# FEU31_Part2.net
KiCad netlist of a schematic drawn in Altium Designer
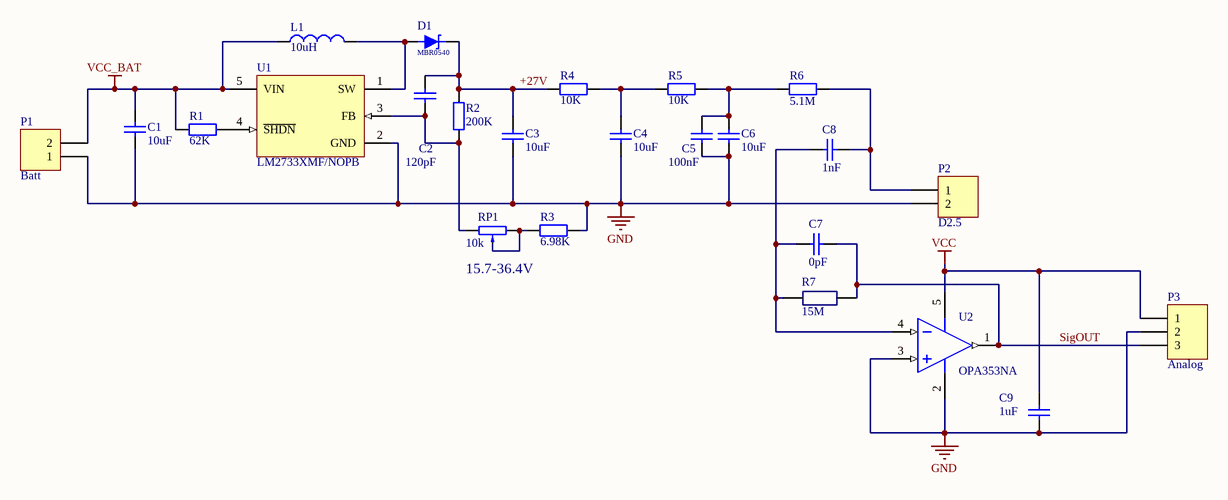
[diagram p0: FEU31_Part2.SchDoc]

(export (version "E")
  (design (tool "Eeschema 10.0.6"))
  (components
    (comp (ref "C1")
      (value "10uF")
      (footprint "Miscellaneous Devices:C1206")
      (description "Capacitor (Semiconductor SIM Model)")
      (fields (field (name "PUBLISHER") "Altium Limited"))
      (libsource (lib "Miscellaneous Devices") (part "Cap Semi"))
    )
    (comp (ref "C2")
      (value "120pF")
      (footprint "1608[0603]")
      (description "Capacitor (Semiconductor SIM Model)")
      (fields (field (name "PUBLISHER") "Altium Limited"))
      (libsource (lib "Miscellaneous Devices") (part "Cap Semi"))
    )
    (comp (ref "C3")
      (value "10uF")
      (footprint "Miscellaneous Devices:C1206")
      (description "Capacitor (Semiconductor SIM Model)")
      (fields (field (name "PUBLISHER") "Altium Limited"))
      (libsource (lib "Miscellaneous Devices") (part "Cap Semi"))
    )
    (comp (ref "C4")
      (value "10uF")
      (footprint "Miscellaneous Devices:C1206")
      (description "Capacitor (Semiconductor SIM Model)")
      (fields (field (name "PUBLISHER") "Altium Limited"))
      (libsource (lib "Miscellaneous Devices") (part "Cap Semi"))
    )
    (comp (ref "C5")
      (value "100nF")
      (footprint "1608[0603]")
      (description "Capacitor (Semiconductor SIM Model)")
      (fields (field (name "PUBLISHER") "Altium Limited"))
      (libsource (lib "Miscellaneous Devices") (part "Cap Semi"))
    )
    (comp (ref "C6")
      (value "10uF")
      (footprint "Miscellaneous Devices:C1206")
      (description "Capacitor (Semiconductor SIM Model)")
      (fields (field (name "PUBLISHER") "Altium Limited"))
      (libsource (lib "Miscellaneous Devices") (part "Cap Semi"))
    )
    (comp (ref "C7")
      (value "0pF")
      (footprint "1608[0603]")
      (description "Capacitor (Semiconductor SIM Model)")
      (fields (field (name "PUBLISHER") "Altium Limited"))
      (libsource (lib "Miscellaneous Devices") (part "Cap Semi"))
    )
    (comp (ref "C8")
      (value "1nF")
      (footprint "1608[0603]")
      (description "Capacitor (Semiconductor SIM Model)")
      (fields (field (name "PUBLISHER") "Altium Limited"))
      (libsource (lib "Miscellaneous Devices") (part "Cap Semi"))
    )
    (comp (ref "C9")
      (value "1uF")
      (footprint "1608[0603]_CAP")
      (description "Capacitor (Semiconductor SIM Model)")
      (fields (field (name "PUBLISHER") "Altium Limited"))
      (libsource (lib "Miscellaneous Devices") (part "Cap Semi"))
    )
    (comp (ref "D1")
      (value "MBR0540")
      (footprint "SOD123")
      (description "SMD 40V 0.5A")
      (libsource (lib "Diodes-Power") (part "MBR0540"))
    )
    (comp (ref "L1")
      (value "10uH")
      (footprint "IFSC1515AHER100M01")
      (description "Inductor")
      (fields (field (name "PUBLISHER") "Altium Limited"))
      (libsource (lib "Miscellaneous Devices") (part "Inductor"))
    )
    (comp (ref "P1")
      (value "Batt")
      (footprint "HDR1X2")
      (description "Header, 2-Pin")
      (fields (field (name "PUBLISHER") "Altium Limited"))
      (libsource (lib "Miscellaneous Connectors") (part "Header 2"))
    )
    (comp (ref "P2")
      (value "D2.5")
      (footprint "HDR1X2")
      (description "Header, 2-Pin")
      (fields (field (name "PUBLISHER") "Altium Limited"))
      (libsource (lib "") (part "Header 2_1"))
    )
    (comp (ref "P3")
      (value "Analog")
      (footprint "HDR1X3")
      (description "Header, 3-Pin")
      (fields (field (name "PUBLISHER") "Altium Limited"))
      (libsource (lib "Miscellaneous Connectors") (part "Header 3"))
    )
    (comp (ref "R1")
      (value "62K")
      (footprint "1608[0603]_RES")
      (description "Resistor")
      (fields (field (name "PUBLISHER") "Altium Limited"))
      (libsource (lib "Miscellaneous Devices") (part "Res2"))
    )
    (comp (ref "R2")
      (value "200K")
      (footprint "1608[0603]_RES")
      (description "Resistor")
      (fields (field (name "PUBLISHER") "Altium Limited"))
      (libsource (lib "") (part "Res2_2"))
    )
    (comp (ref "R3")
      (value "6.98K")
      (footprint "1608[0603]_RES")
      (description "Resistor")
      (fields (field (name "PUBLISHER") "Altium Limited"))
      (libsource (lib "") (part "Res2_1"))
    )
    (comp (ref "R4")
      (value "10K")
      (footprint "1608[0603]_RES")
      (description "Resistor")
      (fields (field (name "PUBLISHER") "Altium Limited"))
      (libsource (lib "Miscellaneous Devices") (part "Res2"))
    )
    (comp (ref "R5")
      (value "10K")
      (footprint "1608[0603]_RES")
      (description "Resistor")
      (fields (field (name "PUBLISHER") "Altium Limited"))
      (libsource (lib "Miscellaneous Devices") (part "Res2"))
    )
    (comp (ref "R6")
      (value "5.1M")
      (footprint "1608[0603]_RES")
      (description "Resistor")
      (fields (field (name "PUBLISHER") "Altium Limited"))
      (libsource (lib "Miscellaneous Devices") (part "Res2"))
    )
    (comp (ref "R7")
      (value "15M")
      (footprint "1608[0603]_RES")
      (libsource (lib "Микрон-3") (part "Resistor 0805"))
    )
    (comp (ref "RP1")
      (value "10k")
      (footprint "3224W")
      (description "Bourns 3296W 0.5W 25 Turns")
      (libsource (lib "Rez-Axial Pot") (part "R-Tr 3296W (64W)"))
    )
    (comp (ref "U1")
      (value "LM2733XMF/NOPB")
      (footprint "MF05A_N")
      (description "0.6/1.6 MHz Boost Converters With 40V Internal FET Switch in 5-pin SOT-23, Pb-Free")
      (fields
        (field (name "MANUFACTURER") "National Semiconductor")
        (field (name "PUBLISHER") "Altium Limited")
      )
      (libsource (lib "NSC Switcher") (part "LM2733XMF/NOPB"))
    )
    (comp (ref "U2")
      (value "OPA353NA")
      (footprint "ADI-RJ-5_N")
      (fields
        (field (name "GENERIC PART NUMBER") "AD8541")
        (field (name "MANUFACTURER") "Analog Devices")
        (field (name "PARTNUMBER") "AD8541ARTZ-R2")
      )
      (libsource (lib "Analog Devices Operational Amplifiers") (part "AD8541ARTZ-R2"))
    )
  )
  (nets
    (net (code "1") (name "/+27V") (class "Default")
      (node (ref "C2") (pin "2") (pinfunction "2_2") (pintype "passive"))
      (node (ref "C3") (pin "1") (pinfunction "1_1") (pintype "passive"))
      (node (ref "D1") (pin "2") (pinfunction "K_2") (pintype "passive"))
      (node (ref "R2") (pin "1") (pinfunction "1_1") (pintype "passive"))
      (node (ref "R4") (pin "2") (pinfunction "2_2") (pintype "passive"))
    )
    (net (code "2") (name "/SigOUT") (class "Default")
      (node (ref "C7") (pin "2") (pinfunction "2_2") (pintype "passive"))
      (node (ref "P3") (pin "3") (pinfunction "3_3") (pintype "passive"))
      (node (ref "R7") (pin "2") (pinfunction "2_2") (pintype "passive"))
      (node (ref "U2") (pin "1") (pinfunction "OUT_A_1") (pintype "output"))
    )
    (net (code "3") (name "GND") (class "Default")
      (node (ref "C1") (pin "2") (pinfunction "2_2") (pintype "passive"))
      (node (ref "C3") (pin "2") (pinfunction "2_2") (pintype "passive"))
      (node (ref "C4") (pin "2") (pinfunction "2_2") (pintype "passive"))
      (node (ref "C5") (pin "1") (pinfunction "1_1") (pintype "passive"))
      (node (ref "C6") (pin "2") (pinfunction "2_2") (pintype "passive"))
      (node (ref "C9") (pin "2") (pinfunction "2_2") (pintype "passive"))
      (node (ref "P1") (pin "1") (pinfunction "1_1") (pintype "passive"))
      (node (ref "P2") (pin "2") (pinfunction "2_2") (pintype "passive"))
      (node (ref "P3") (pin "2") (pinfunction "2_2") (pintype "passive"))
      (node (ref "R3") (pin "2") (pinfunction "2_2") (pintype "passive"))
      (node (ref "U1") (pin "2") (pinfunction "GND_2") (pintype "power_in"))
      (node (ref "U2") (pin "2") (pinfunction "-V_2") (pintype "power_in"))
      (node (ref "U2") (pin "3") (pinfunction "+IN_A_3") (pintype "input"))
    )
    (net (code "4") (name "Net-(C4-Pad1)") (class "Default")
      (node (ref "C4") (pin "1") (pinfunction "1_1") (pintype "passive"))
      (node (ref "R4") (pin "1") (pinfunction "1_1") (pintype "passive"))
      (node (ref "R5") (pin "2") (pinfunction "2_2") (pintype "passive"))
    )
    (net (code "5") (name "Net-(C5-Pad2)") (class "Default")
      (node (ref "C5") (pin "2") (pinfunction "2_2") (pintype "passive"))
      (node (ref "C6") (pin "1") (pinfunction "1_1") (pintype "passive"))
      (node (ref "R5") (pin "1") (pinfunction "1_1") (pintype "passive"))
      (node (ref "R6") (pin "2") (pinfunction "2_2") (pintype "passive"))
    )
    (net (code "6") (name "Net-(C8-Pad1)") (class "Default")
      (node (ref "C8") (pin "1") (pinfunction "1_1") (pintype "passive"))
      (node (ref "P2") (pin "1") (pinfunction "1_1") (pintype "passive"))
      (node (ref "R6") (pin "1") (pinfunction "1_1") (pintype "passive"))
    )
    (net (code "7") (name "Net-(D1-A)") (class "Default")
      (node (ref "D1") (pin "1") (pinfunction "A_1") (pintype "passive"))
      (node (ref "L1") (pin "2") (pinfunction "2_2") (pintype "passive"))
      (node (ref "U1") (pin "1") (pinfunction "SW_1") (pintype "power_in"))
    )
    (net (code "8") (name "Net-(R3-Pad1)") (class "Default")
      (node (ref "R3") (pin "1") (pinfunction "1_1") (pintype "passive"))
      (node (ref "RP1") (pin "1") (pinfunction "1_1") (pintype "passive"))
      (node (ref "RP1") (pin "2") (pinfunction "2_2") (pintype "passive"))
    )
    (net (code "9") (name "Net-(R7-A)") (class "Default")
      (node (ref "C7") (pin "1") (pinfunction "1_1") (pintype "passive"))
      (node (ref "C8") (pin "2") (pinfunction "2_2") (pintype "passive"))
      (node (ref "R7") (pin "1") (pinfunction "A_1") (pintype "passive"))
      (node (ref "U2") (pin "4") (pinfunction "-IN_A_4") (pintype "input"))
    )
    (net (code "10") (name "Net-(U1-FB)") (class "Default")
      (node (ref "C2") (pin "1") (pinfunction "1_1") (pintype "passive"))
      (node (ref "R2") (pin "2") (pinfunction "2_2") (pintype "passive"))
      (node (ref "RP1") (pin "3") (pinfunction "3_3") (pintype "passive"))
      (node (ref "U1") (pin "3") (pinfunction "FB_3") (pintype "input"))
    )
    (net (code "11") (name "Net-(U1-~{SHDN})") (class "Default")
      (node (ref "R1") (pin "1") (pinfunction "1_1") (pintype "passive"))
      (node (ref "U1") (pin "4") (pinfunction "~{SHDN}_4") (pintype "input"))
    )
    (net (code "12") (name "VCC") (class "Default")
      (node (ref "C9") (pin "1") (pinfunction "1_1") (pintype "passive"))
      (node (ref "P3") (pin "1") (pinfunction "1_1") (pintype "passive"))
      (node (ref "U2") (pin "5") (pinfunction "+V_5") (pintype "power_in"))
    )
    (net (code "13") (name "VCC_BAT") (class "Default")
      (node (ref "C1") (pin "1") (pinfunction "1_1") (pintype "passive"))
      (node (ref "L1") (pin "1") (pinfunction "1_1") (pintype "passive"))
      (node (ref "P1") (pin "2") (pinfunction "2_2") (pintype "passive"))
      (node (ref "R1") (pin "2") (pinfunction "2_2") (pintype "passive"))
      (node (ref "U1") (pin "5") (pinfunction "VIN_5") (pintype "power_in"))
    )
  )
)
